# scales.net
KiCad netlist of a schematic drawn in EAGLE
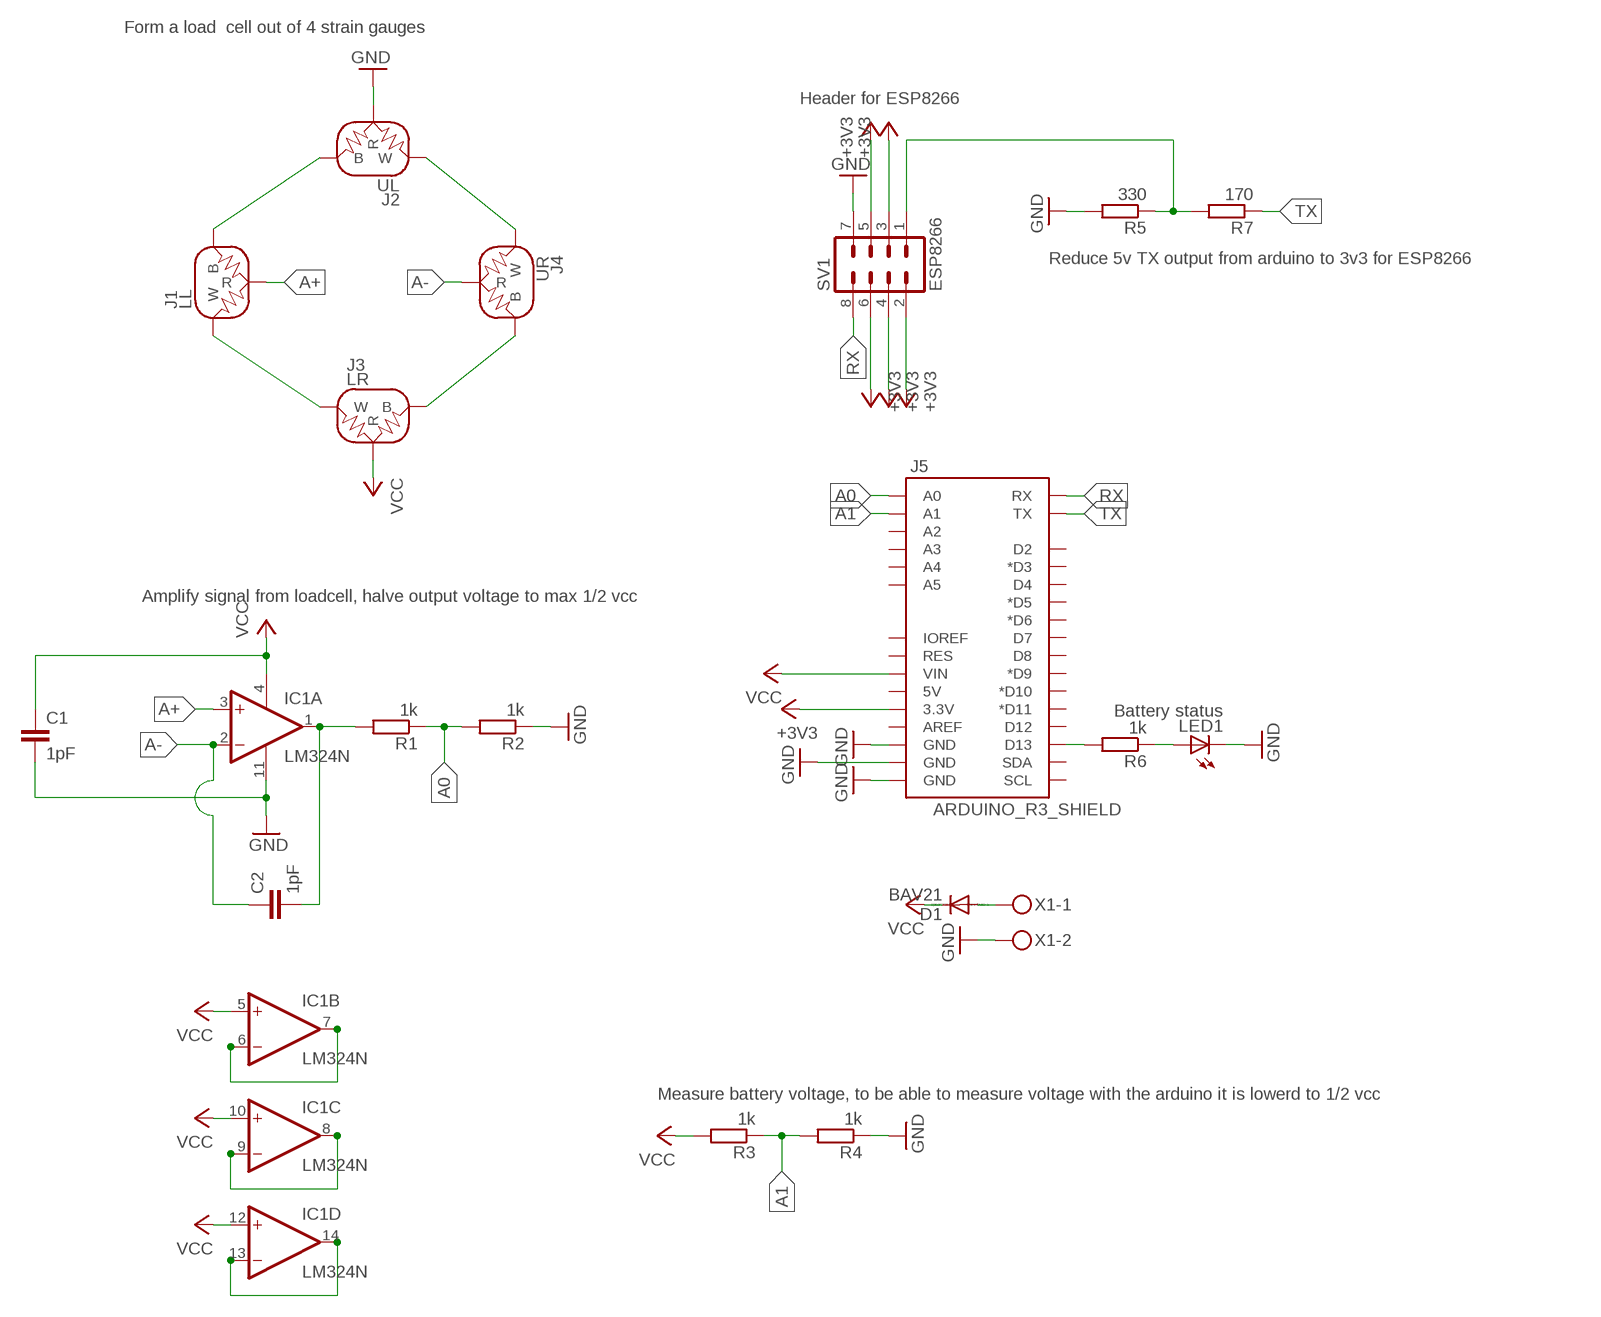
[diagram p0: schematic, sheet 1]

(export (version "E")
  (design (tool "Eeschema 10.0.6"))
  (components
    (comp (ref "C1")
      (value "1pF")
      (footprint "eagle-import:C025-024X044")
      (libsource (lib "eagle-import") (part "C-EU025-024X044"))
    )
    (comp (ref "C2")
      (value "1pF")
      (footprint "eagle-import:C025-024X044")
      (libsource (lib "eagle-import") (part "C-EU025-024X044"))
    )
    (comp (ref "D1")
      (value "BAV21")
      (footprint "eagle-import:DO35-10")
      (libsource (lib "eagle-import") (part "BAV21"))
    )
    (comp (ref "IC1")
      (value "LM324N")
      (footprint "eagle-import:DIL14")
      (fields
        (field (name "MF") "STMICROELECTRONICS")
        (field (name "MPN") "LM324AN")
        (field (name "OC_FARNELL") "1467654")
      )
      (libsource (lib "eagle-import") (part "LM324N"))
    )
    (comp (ref "J1")
      (value "LL")
      (footprint "eagle-import:1X03")
      (libsource (lib "eagle-import") (part "LOAD_CELL1X03-PTH"))
    )
    (comp (ref "J2")
      (value "UL")
      (footprint "eagle-import:1X03")
      (libsource (lib "eagle-import") (part "LOAD_CELL1X03-PTH"))
    )
    (comp (ref "J3")
      (value "LR")
      (footprint "eagle-import:1X03")
      (libsource (lib "eagle-import") (part "LOAD_CELL1X03-PTH"))
    )
    (comp (ref "J4")
      (value "UR")
      (footprint "eagle-import:1X03")
      (libsource (lib "eagle-import") (part "LOAD_CELL1X03-PTH"))
    )
    (comp (ref "J5")
      (value "ARDUINO_R3_SHIELD")
      (footprint "eagle-import:UNO_R3_SHIELD")
      (libsource (lib "eagle-import") (part "ARDUINO_R3_SHIELD"))
    )
    (comp (ref "LED1")
      (value "Battery status")
      (footprint "eagle-import:LED5MM")
      (libsource (lib "eagle-import") (part "LED5MM"))
    )
    (comp (ref "R1")
      (value "1k")
      (footprint "eagle-import:0204_5")
      (fields (field (name "MF") "PANASONIC ELECTRONIC COMPONENTS") (field (name "MPN") "ERG1SJ102"))
      (libsource (lib "eagle-import") (part "R-EU_0204/5"))
    )
    (comp (ref "R2")
      (value "1k")
      (footprint "eagle-import:0204_5")
      (fields (field (name "MF") "PANASONIC ELECTRONIC COMPONENTS") (field (name "MPN") "ERG1SJ102"))
      (libsource (lib "eagle-import") (part "R-EU_0204/5"))
    )
    (comp (ref "R3")
      (value "1k")
      (footprint "eagle-import:0204_5")
      (fields (field (name "MF") "PANASONIC ELECTRONIC COMPONENTS") (field (name "MPN") "ERG1SJ102"))
      (libsource (lib "eagle-import") (part "R-EU_0204/5"))
    )
    (comp (ref "R4")
      (value "1k")
      (footprint "eagle-import:0204_5")
      (fields (field (name "MF") "PANASONIC ELECTRONIC COMPONENTS") (field (name "MPN") "ERG1SJ102"))
      (libsource (lib "eagle-import") (part "R-EU_0204/5"))
    )
    (comp (ref "R5")
      (value "330")
      (footprint "eagle-import:0204_5")
      (fields (field (name "MF") "PANASONIC ELECTRONIC COMPONENTS") (field (name "MPN") "ERG1SJ102"))
      (libsource (lib "eagle-import") (part "R-EU_0204/5"))
    )
    (comp (ref "R6")
      (value "1k")
      (footprint "eagle-import:0204_5")
      (fields (field (name "MF") "PANASONIC ELECTRONIC COMPONENTS") (field (name "MPN") "ERG1SJ102"))
      (libsource (lib "eagle-import") (part "R-EU_0204/5"))
    )
    (comp (ref "R7")
      (value "170")
      (footprint "eagle-import:0204_5")
      (fields (field (name "MF") "PANASONIC ELECTRONIC COMPONENTS") (field (name "MPN") "ERG1SJ102"))
      (libsource (lib "eagle-import") (part "R-EU_0204/5"))
    )
    (comp (ref "SV1")
      (value "ESP8266")
      (footprint "eagle-import:MA04-2")
      (fields
        (field (name "MF") "GLOBAL CONNECTOR TECHNOLOGY")
        (field (name "MPN") "BD060-08-A-N-0230-L-G")
        (field (name "OC_FARNELL") "1798806")
      )
      (libsource (lib "eagle-import") (part "MA04-2"))
    )
    (comp (ref "X1")
      (value "MKDSN1,5/2-5,08")
      (footprint "eagle-import:MKDSN1,5_2-5,08")
      (libsource (lib "eagle-import") (part "MKDSN1,5/2-5,08"))
    )
  )
  (nets
    (net (code "1") (name "+3V3") (class "Default")
      (node (ref "J5") (pin "3.3V") (pinfunction "3.3V_3.3V") (pintype "bidirectional"))
      (node (ref "SV1") (pin "2") (pinfunction "2_2") (pintype "passive"))
      (node (ref "SV1") (pin "3") (pinfunction "3_3") (pintype "passive"))
      (node (ref "SV1") (pin "4") (pinfunction "4_4") (pintype "passive"))
      (node (ref "SV1") (pin "5") (pinfunction "5_5") (pintype "passive"))
      (node (ref "SV1") (pin "6") (pinfunction "6_6") (pintype "passive"))
    )
    (net (code "2") (name "A+") (class "Default")
      (node (ref "IC1") (pin "3") (pinfunction "+IN_3") (pintype "input"))
      (node (ref "J1") (pin "3") (pinfunction "R_3") (pintype "passive"))
    )
    (net (code "3") (name "A-") (class "Default")
      (node (ref "C2") (pin "1") (pinfunction "1_1") (pintype "passive"))
      (node (ref "IC1") (pin "2") (pinfunction "-IN_2") (pintype "input"))
      (node (ref "J4") (pin "3") (pinfunction "R_3") (pintype "passive"))
    )
    (net (code "4") (name "A0") (class "Default")
      (node (ref "J5") (pin "A0") (pinfunction "A0_A0") (pintype "bidirectional"))
      (node (ref "R1") (pin "1") (pinfunction "1_1") (pintype "passive"))
      (node (ref "R2") (pin "2") (pinfunction "2_2") (pintype "passive"))
    )
    (net (code "5") (name "A1") (class "Default")
      (node (ref "J5") (pin "A1") (pinfunction "A1_A1") (pintype "bidirectional"))
      (node (ref "R3") (pin "1") (pinfunction "1_1") (pintype "passive"))
      (node (ref "R4") (pin "2") (pinfunction "2_2") (pintype "passive"))
    )
    (net (code "6") (name "GND") (class "Default")
      (node (ref "C1") (pin "2") (pinfunction "2_2") (pintype "passive"))
      (node (ref "IC1") (pin "11") (pinfunction "V-_11") (pintype "power_in"))
      (node (ref "J2") (pin "3") (pinfunction "R_3") (pintype "passive"))
      (node (ref "J5") (pin "GND@0") (pinfunction "GND_GND@0") (pintype "bidirectional"))
      (node (ref "J5") (pin "GND@1") (pinfunction "GND_GND@1") (pintype "bidirectional"))
      (node (ref "J5") (pin "GND@2") (pinfunction "GND_GND@2") (pintype "bidirectional"))
      (node (ref "LED1") (pin "K") (pinfunction "C_K") (pintype "passive"))
      (node (ref "R2") (pin "1") (pinfunction "1_1") (pintype "passive"))
      (node (ref "R4") (pin "1") (pinfunction "1_1") (pintype "passive"))
      (node (ref "R5") (pin "2") (pinfunction "2_2") (pintype "passive"))
      (node (ref "SV1") (pin "7") (pinfunction "7_7") (pintype "passive"))
      (node (ref "X1") (pin "2") (pinfunction "KL_2") (pintype "passive"))
    )
    (net (code "7") (name "Net-(IC1A-OUT)") (class "Default")
      (node (ref "C2") (pin "2") (pinfunction "2_2") (pintype "passive"))
      (node (ref "IC1") (pin "1") (pinfunction "OUT_1") (pintype "output"))
      (node (ref "R1") (pin "2") (pinfunction "2_2") (pintype "passive"))
    )
    (net (code "8") (name "Net-(IC1B--IN)") (class "Default")
      (node (ref "IC1") (pin "6") (pinfunction "-IN_6") (pintype "input"))
      (node (ref "IC1") (pin "7") (pinfunction "OUT_7") (pintype "output"))
    )
    (net (code "9") (name "Net-(IC1C--IN)") (class "Default")
      (node (ref "IC1") (pin "8") (pinfunction "OUT_8") (pintype "output"))
      (node (ref "IC1") (pin "9") (pinfunction "-IN_9") (pintype "input"))
    )
    (net (code "10") (name "Net-(IC1D--IN)") (class "Default")
      (node (ref "IC1") (pin "13") (pinfunction "-IN_13") (pintype "input"))
      (node (ref "IC1") (pin "14") (pinfunction "OUT_14") (pintype "output"))
    )
    (net (code "11") (name "Net-(J1-B)") (class "Default")
      (node (ref "J1") (pin "1") (pinfunction "B_1") (pintype "passive"))
      (node (ref "J2") (pin "1") (pinfunction "B_1") (pintype "passive"))
    )
    (net (code "12") (name "Net-(J1-W)") (class "Default")
      (node (ref "J1") (pin "2") (pinfunction "W_2") (pintype "passive"))
      (node (ref "J3") (pin "2") (pinfunction "W_2") (pintype "passive"))
    )
    (net (code "13") (name "Net-(J2-W)") (class "Default")
      (node (ref "J2") (pin "2") (pinfunction "W_2") (pintype "passive"))
      (node (ref "J4") (pin "2") (pinfunction "W_2") (pintype "passive"))
    )
    (net (code "14") (name "Net-(J3-B)") (class "Default")
      (node (ref "J3") (pin "1") (pinfunction "B_1") (pintype "passive"))
      (node (ref "J4") (pin "1") (pinfunction "B_1") (pintype "passive"))
    )
    (net (code "15") (name "Net-(J5-PadD13)") (class "Default")
      (node (ref "J5") (pin "D13") (pinfunction "D13_D13") (pintype "bidirectional"))
      (node (ref "R6") (pin "2") (pinfunction "2_2") (pintype "passive"))
    )
    (net (code "16") (name "Net-(LED1-PadA)") (class "Default")
      (node (ref "LED1") (pin "A") (pinfunction "A_A") (pintype "passive"))
      (node (ref "R6") (pin "1") (pinfunction "1_1") (pintype "passive"))
    )
    (net (code "17") (name "Net-(R5-Pad1)") (class "Default")
      (node (ref "R5") (pin "1") (pinfunction "1_1") (pintype "passive"))
      (node (ref "R7") (pin "2") (pinfunction "2_2") (pintype "passive"))
      (node (ref "SV1") (pin "1") (pinfunction "1_1") (pintype "passive"))
    )
    (net (code "18") (name "Net-(X1A-KL)") (class "Default")
      (node (ref "D1") (pin "A") (pinfunction "A_A") (pintype "passive"))
      (node (ref "X1") (pin "1") (pinfunction "KL_1") (pintype "passive"))
    )
    (net (code "19") (name "RX") (class "Default")
      (node (ref "J5") (pin "RX") (pinfunction "RX_RX") (pintype "bidirectional"))
      (node (ref "SV1") (pin "8") (pinfunction "8_8") (pintype "passive"))
    )
    (net (code "20") (name "TX") (class "Default")
      (node (ref "J5") (pin "TX") (pinfunction "TX_TX") (pintype "bidirectional"))
      (node (ref "R7") (pin "1") (pinfunction "1_1") (pintype "passive"))
    )
    (net (code "21") (name "VCC") (class "Default")
      (node (ref "C1") (pin "1") (pinfunction "1_1") (pintype "passive"))
      (node (ref "D1") (pin "C") (pinfunction "C_C") (pintype "passive"))
      (node (ref "IC1") (pin "10") (pinfunction "+IN_10") (pintype "input"))
      (node (ref "IC1") (pin "12") (pinfunction "+IN_12") (pintype "input"))
      (node (ref "IC1") (pin "4") (pinfunction "V+_4") (pintype "power_in"))
      (node (ref "IC1") (pin "5") (pinfunction "+IN_5") (pintype "input"))
      (node (ref "J3") (pin "3") (pinfunction "R_3") (pintype "passive"))
      (node (ref "J5") (pin "VIN") (pinfunction "VIN_VIN") (pintype "bidirectional"))
      (node (ref "R3") (pin "2") (pinfunction "2_2") (pintype "passive"))
    )
    (net (code "22") (name "unconnected-(J5-*D3-PadD3)") (class "Default")
      (node (ref "J5") (pin "D3") (pinfunction "*D3_D3") (pintype "bidirectional"))
    )
    (net (code "23") (name "unconnected-(J5-*D5-PadD5)") (class "Default")
      (node (ref "J5") (pin "D5") (pinfunction "*D5_D5") (pintype "bidirectional"))
    )
    (net (code "24") (name "unconnected-(J5-*D6-PadD6)") (class "Default")
      (node (ref "J5") (pin "D6") (pinfunction "*D6_D6") (pintype "bidirectional"))
    )
    (net (code "25") (name "unconnected-(J5-*D9-PadD9)") (class "Default")
      (node (ref "J5") (pin "D9") (pinfunction "*D9_D9") (pintype "bidirectional"))
    )
    (net (code "26") (name "unconnected-(J5-*D10-PadD10)") (class "Default")
      (node (ref "J5") (pin "D10") (pinfunction "*D10_D10") (pintype "bidirectional"))
    )
    (net (code "27") (name "unconnected-(J5-*D11-PadD11)") (class "Default")
      (node (ref "J5") (pin "D11") (pinfunction "*D11_D11") (pintype "bidirectional"))
    )
    (net (code "28") (name "unconnected-(J5-Pad5V)") (class "Default")
      (node (ref "J5") (pin "5V") (pinfunction "5V_5V") (pintype "bidirectional"))
    )
    (net (code "29") (name "unconnected-(J5-PadA2)") (class "Default")
      (node (ref "J5") (pin "A2") (pinfunction "A2_A2") (pintype "bidirectional"))
    )
    (net (code "30") (name "unconnected-(J5-PadA3)") (class "Default")
      (node (ref "J5") (pin "A3") (pinfunction "A3_A3") (pintype "bidirectional"))
    )
    (net (code "31") (name "unconnected-(J5-PadA4)") (class "Default")
      (node (ref "J5") (pin "A4") (pinfunction "A4_A4") (pintype "bidirectional"))
    )
    (net (code "32") (name "unconnected-(J5-PadA5)") (class "Default")
      (node (ref "J5") (pin "A5") (pinfunction "A5_A5") (pintype "bidirectional"))
    )
    (net (code "33") (name "unconnected-(J5-PadAREF)") (class "Default")
      (node (ref "J5") (pin "AREF") (pinfunction "AREF_AREF") (pintype "bidirectional"))
    )
    (net (code "34") (name "unconnected-(J5-PadD2)") (class "Default")
      (node (ref "J5") (pin "D2") (pinfunction "D2_D2") (pintype "bidirectional"))
    )
    (net (code "35") (name "unconnected-(J5-PadD4)") (class "Default")
      (node (ref "J5") (pin "D4") (pinfunction "D4_D4") (pintype "bidirectional"))
    )
    (net (code "36") (name "unconnected-(J5-PadD7)") (class "Default")
      (node (ref "J5") (pin "D7") (pinfunction "D7_D7") (pintype "bidirectional"))
    )
    (net (code "37") (name "unconnected-(J5-PadD8)") (class "Default")
      (node (ref "J5") (pin "D8") (pinfunction "D8_D8") (pintype "bidirectional"))
    )
    (net (code "38") (name "unconnected-(J5-PadD12)") (class "Default")
      (node (ref "J5") (pin "D12") (pinfunction "D12_D12") (pintype "bidirectional"))
    )
    (net (code "39") (name "unconnected-(J5-PadIOREF)") (class "Default")
      (node (ref "J5") (pin "IOREF") (pinfunction "IOREF_IOREF") (pintype "bidirectional"))
    )
    (net (code "40") (name "unconnected-(J5-PadRES)") (class "Default")
      (node (ref "J5") (pin "RES") (pinfunction "RES_RES") (pintype "bidirectional"))
    )
    (net (code "41") (name "unconnected-(J5-PadSCL)") (class "Default")
      (node (ref "J5") (pin "SCL") (pinfunction "SCL_SCL") (pintype "bidirectional"))
    )
    (net (code "42") (name "unconnected-(J5-PadSDA)") (class "Default")
      (node (ref "J5") (pin "SDA") (pinfunction "SDA_SDA") (pintype "bidirectional"))
    )
  )
)
